# o18_irTransmitter-v03_3_3.net
KiCad netlist of a schematic drawn in EAGLE
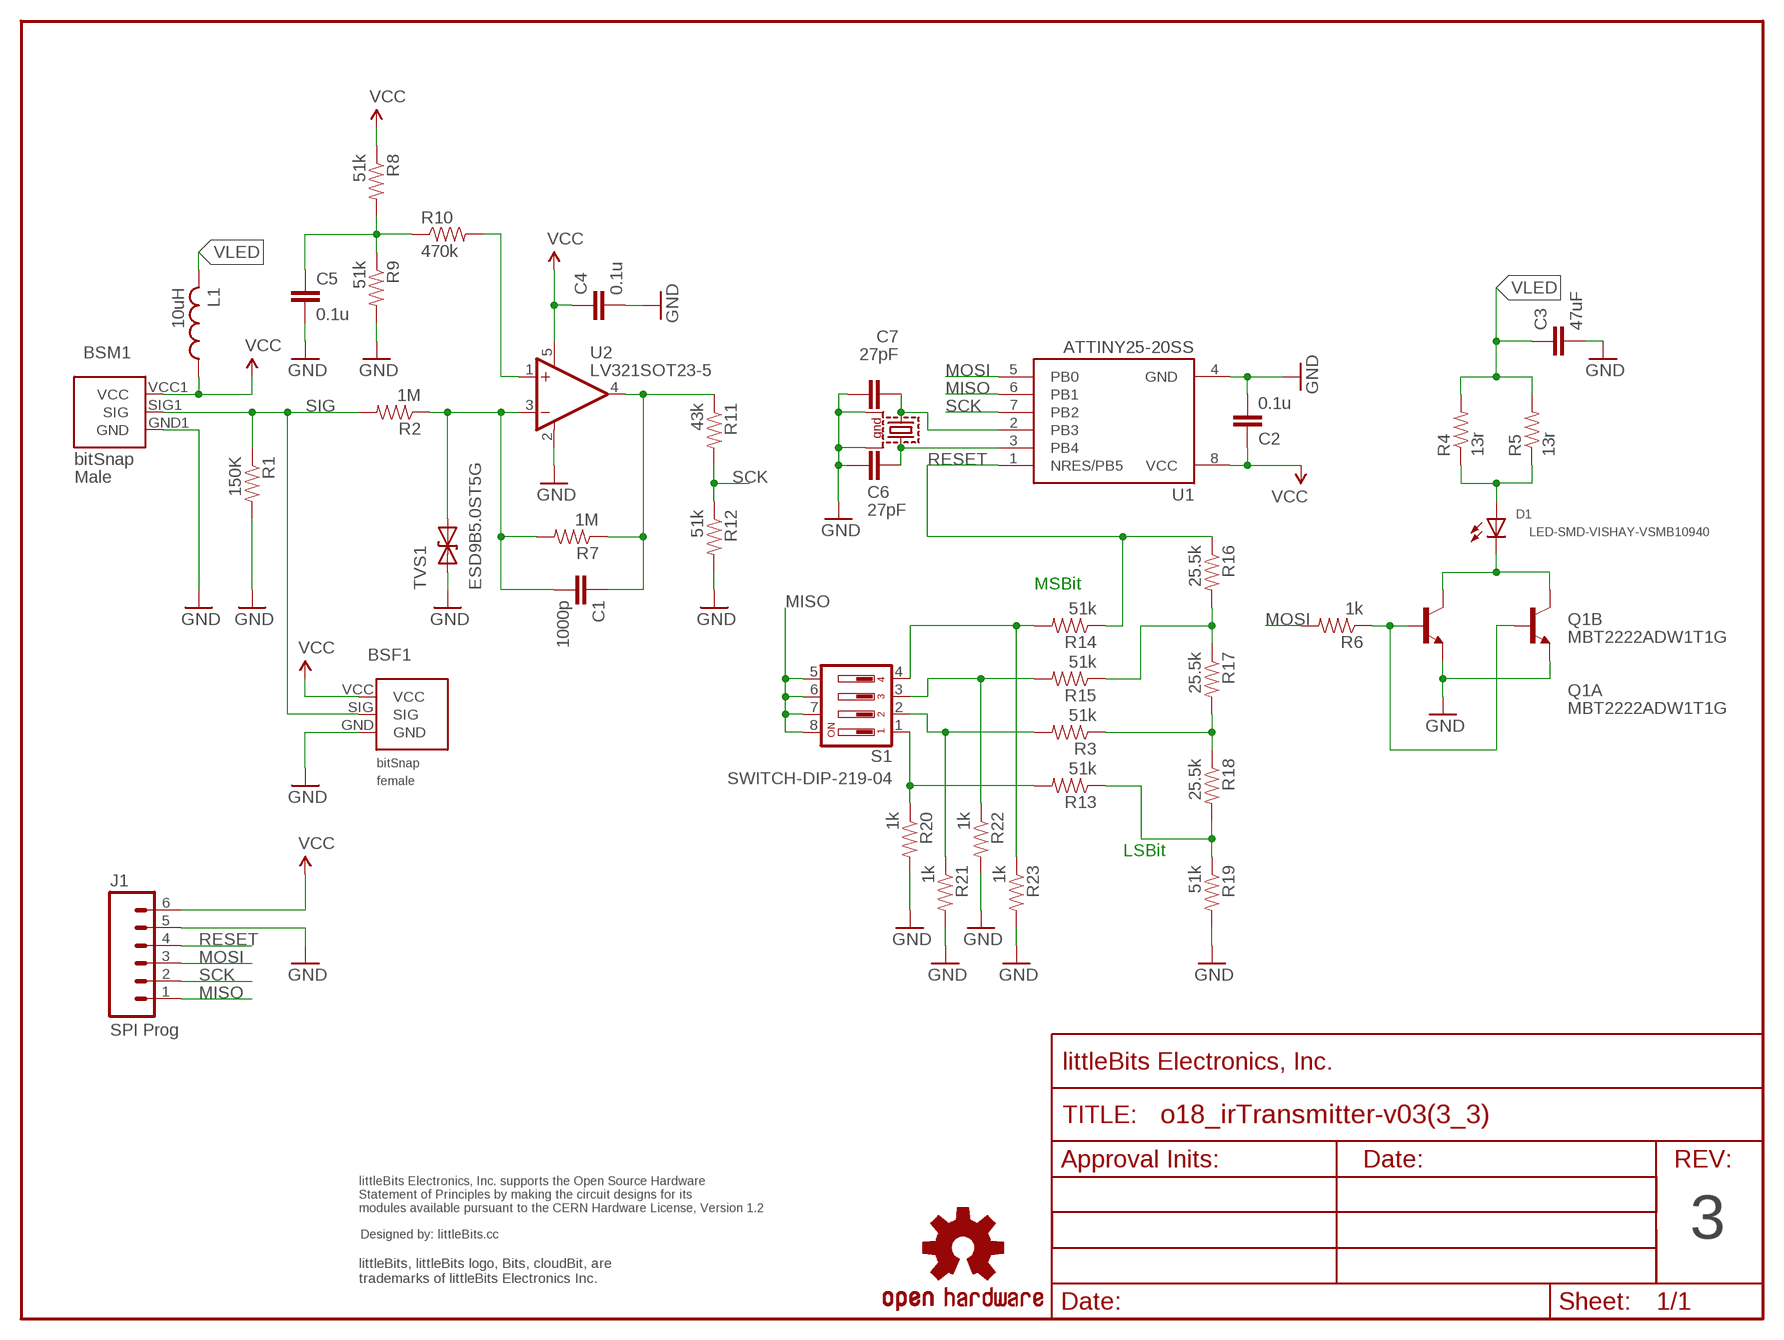
[diagram p0: schematic, sheet 1]

(export (version "E")
  (design (tool "Eeschema 10.0.6"))
  (components
    (comp (ref "BSF1")
      (value "BITSNAP_V03_FEMALE")
      (footprint "eagle-import:BITSNAP_V03_FEMALE")
      (libsource (lib "eagle-import") (part "BITSNAP_V03_FEMALE"))
    )
    (comp (ref "BSM1")
      (value "BITSNAP_V03_MALE")
      (footprint "eagle-import:BITSNAP_V03_MALE")
      (libsource (lib "eagle-import") (part "BITSNAP_V03_MALE"))
    )
    (comp (ref "C1")
      (value "1000p")
      (footprint "eagle-import:CAP-0402")
      (libsource (lib "eagle-import") (part "CAPCAP-0402"))
    )
    (comp (ref "C2")
      (value "0.1u")
      (footprint "eagle-import:CAP-0402")
      (libsource (lib "eagle-import") (part "CAPCAP-0402"))
    )
    (comp (ref "C3")
      (value "47uF")
      (footprint "eagle-import:CAP-1206")
      (libsource (lib "eagle-import") (part "CAPCAP-1206"))
    )
    (comp (ref "C4")
      (value "0.1u")
      (footprint "eagle-import:CAP-0402")
      (libsource (lib "eagle-import") (part "CAPCAP-0402"))
    )
    (comp (ref "C5")
      (value "0.1u")
      (footprint "eagle-import:CAP-0402")
      (libsource (lib "eagle-import") (part "CAPCAP-0402"))
    )
    (comp (ref "C6")
      (value "27pF")
      (footprint "eagle-import:CAP-0402")
      (libsource (lib "eagle-import") (part "CAPCAP-0402"))
    )
    (comp (ref "C7")
      (value "27pF")
      (footprint "eagle-import:CAP-0402")
      (libsource (lib "eagle-import") (part "CAPCAP-0402"))
    )
    (comp (ref "D1")
      (value "LED-SMD-VISHAY-VSMB10940")
      (footprint "eagle-import:LED-SMD-VISHAY-VSMB10940")
      (libsource (lib "eagle-import") (part "LED-SMD-VISHAY-VSMB10940"))
    )
    (comp (ref "J1")
      (value "SPI Prog")
      (footprint "eagle-import:SIP6-SM-0.1IN-NOS.S-MIN")
      (libsource (lib "eagle-import") (part "HRD-60.1INCH_NO_SILKSCREEN_SMALL"))
    )
    (comp (ref "L1")
      (value "10uH")
      (footprint "eagle-import:IND-0805")
      (libsource (lib "eagle-import") (part "INDUCTOR-SMT0805"))
    )
    (comp (ref "Q1")
      (value "MBT2222ADW1T1G")
      (footprint "eagle-import:SOT-363_ONSEMI")
      (libsource (lib "eagle-import") (part "TRANS-BJT_NPN-DUAL-MBT2222ADW1T1-D"))
    )
    (comp (ref "R1")
      (value "150K")
      (footprint "eagle-import:RES-0402")
      (libsource (lib "eagle-import") (part "RESISTOR0402"))
    )
    (comp (ref "R2")
      (value "1M")
      (footprint "eagle-import:RES-0402")
      (libsource (lib "eagle-import") (part "RESISTOR0402"))
    )
    (comp (ref "R3")
      (value "51k")
      (footprint "eagle-import:RES-0402")
      (libsource (lib "eagle-import") (part "RESISTOR0402"))
    )
    (comp (ref "R4")
      (value "13r")
      (footprint "eagle-import:RES-0603")
      (libsource (lib "eagle-import") (part "RESISTOR0603"))
    )
    (comp (ref "R5")
      (value "13r")
      (footprint "eagle-import:RES-0603")
      (libsource (lib "eagle-import") (part "RESISTOR0603"))
    )
    (comp (ref "R6")
      (value "1k")
      (footprint "eagle-import:RES-0402")
      (libsource (lib "eagle-import") (part "RESISTOR0402"))
    )
    (comp (ref "R7")
      (value "1M")
      (footprint "eagle-import:RES-0402")
      (libsource (lib "eagle-import") (part "RESISTOR0402"))
    )
    (comp (ref "R8")
      (value "51k")
      (footprint "eagle-import:RES-0402")
      (libsource (lib "eagle-import") (part "RESISTOR0402"))
    )
    (comp (ref "R9")
      (value "51k")
      (footprint "eagle-import:RES-0402")
      (libsource (lib "eagle-import") (part "RESISTOR0402"))
    )
    (comp (ref "R10")
      (value "470k")
      (footprint "eagle-import:RES-0402")
      (libsource (lib "eagle-import") (part "RESISTOR0402"))
    )
    (comp (ref "R11")
      (value "43k")
      (footprint "eagle-import:RES-0402")
      (libsource (lib "eagle-import") (part "RESISTOR0402"))
    )
    (comp (ref "R12")
      (value "51k")
      (footprint "eagle-import:RES-0402")
      (libsource (lib "eagle-import") (part "RESISTOR0402"))
    )
    (comp (ref "R13")
      (value "51k")
      (footprint "eagle-import:RES-0402")
      (libsource (lib "eagle-import") (part "RESISTOR0402"))
    )
    (comp (ref "R14")
      (value "51k")
      (footprint "eagle-import:RES-0402")
      (libsource (lib "eagle-import") (part "RESISTOR0402"))
    )
    (comp (ref "R15")
      (value "51k")
      (footprint "eagle-import:RES-0402")
      (libsource (lib "eagle-import") (part "RESISTOR0402"))
    )
    (comp (ref "R16")
      (value "25.5k")
      (footprint "eagle-import:RES-0402")
      (libsource (lib "eagle-import") (part "RESISTOR0402"))
    )
    (comp (ref "R17")
      (value "25.5k")
      (footprint "eagle-import:RES-0402")
      (libsource (lib "eagle-import") (part "RESISTOR0402"))
    )
    (comp (ref "R18")
      (value "25.5k")
      (footprint "eagle-import:RES-0402")
      (libsource (lib "eagle-import") (part "RESISTOR0402"))
    )
    (comp (ref "R19")
      (value "51k")
      (footprint "eagle-import:RES-0402")
      (libsource (lib "eagle-import") (part "RESISTOR0402"))
    )
    (comp (ref "R20")
      (value "1k")
      (footprint "eagle-import:RES-0402")
      (libsource (lib "eagle-import") (part "RESISTOR0402"))
    )
    (comp (ref "R21")
      (value "1k")
      (footprint "eagle-import:RES-0402")
      (libsource (lib "eagle-import") (part "RESISTOR0402"))
    )
    (comp (ref "R22")
      (value "1k")
      (footprint "eagle-import:RES-0402")
      (libsource (lib "eagle-import") (part "RESISTOR0402"))
    )
    (comp (ref "R23")
      (value "1k")
      (footprint "eagle-import:RES-0402")
      (libsource (lib "eagle-import") (part "RESISTOR0402"))
    )
    (comp (ref "S1")
      (value "SWITCH-DIP-219-04")
      (footprint "eagle-import:CTS-219-04")
      (libsource (lib "eagle-import") (part "SWITCH-DIP-219-04"))
    )
    (comp (ref "TVS1")
      (value "ESD9B5.0ST5G")
      (footprint "eagle-import:SOD-923")
      (libsource (lib "eagle-import") (part "DIODE-TVSSOD-923"))
    )
    (comp (ref "U$16")
      (value "OSHWCREDIT")
      (footprint "eagle-import:OSHWCREDIT")
      (libsource (lib "eagle-import") (part "OSHWCREDIT"))
    )
    (comp (ref "U$26")
      (value "FRAME-LETTER-OHWOHW")
      (footprint "eagle-import:FABDWG01-OHW")
      (libsource (lib "eagle-import") (part "FRAME-LETTER-OHWOHW"))
    )
    (comp (ref "U$27")
      (value "OSHW-LOGOL")
      (footprint "eagle-import:OSHW-LOGO-L")
      (libsource (lib "eagle-import") (part "OSHW-LOGOL"))
    )
    (comp (ref "U1")
      (value "ATTINY25-20SS")
      (footprint "eagle-import:SOIC08_JEDEC_150MIL")
      (libsource (lib "eagle-import") (part "ATTINY25SS-20"))
    )
    (comp (ref "U2")
      (value "LV321SOT23-5")
      (footprint "eagle-import:SOT23-5")
      (libsource (lib "eagle-import") (part "LV321SOT23-5"))
    )
    (comp (ref "X1")
      (value "7B-8.000MAAJ-T")
      (footprint "eagle-import:CRYSTAL-SMD-7B-SERIES-5X3.2MM")
      (fields (field (name "MFG") "TXC") (field (name "MPN") "7B SERIES"))
      (libsource (lib "eagle-import") (part "CRYSTAL-SMD-7B-SERIES-TXC"))
    )
  )
  (nets
    (net (code "1") (name "/MISO") (class "Default")
      (node (ref "J1") (pin "1") (pinfunction "1_1") (pintype "passive"))
      (node (ref "S1") (pin "5") (pinfunction "5_5") (pintype "passive"))
      (node (ref "S1") (pin "6") (pinfunction "6_6") (pintype "passive"))
      (node (ref "S1") (pin "7") (pinfunction "7_7") (pintype "passive"))
      (node (ref "S1") (pin "8") (pinfunction "8_8") (pintype "passive"))
      (node (ref "U1") (pin "6") (pinfunction "PB1_6") (pintype "bidirectional"))
    )
    (net (code "2") (name "/MOSI") (class "Default")
      (node (ref "J1") (pin "3") (pinfunction "3_3") (pintype "passive"))
      (node (ref "R6") (pin "2") (pinfunction "2_2") (pintype "passive"))
      (node (ref "U1") (pin "5") (pinfunction "PB0_5") (pintype "bidirectional"))
    )
    (net (code "3") (name "/RESET") (class "Default")
      (node (ref "J1") (pin "4") (pinfunction "4_4") (pintype "passive"))
      (node (ref "R14") (pin "1") (pinfunction "1_1") (pintype "passive"))
      (node (ref "R16") (pin "1") (pinfunction "1_1") (pintype "passive"))
      (node (ref "U1") (pin "1") (pinfunction "NRES/PB5_1") (pintype "bidirectional"))
    )
    (net (code "4") (name "/SCK") (class "Default")
      (node (ref "J1") (pin "2") (pinfunction "2_2") (pintype "passive"))
      (node (ref "R11") (pin "2") (pinfunction "2_2") (pintype "passive"))
      (node (ref "R12") (pin "1") (pinfunction "1_1") (pintype "passive"))
      (node (ref "U1") (pin "7") (pinfunction "PB2_7") (pintype "bidirectional"))
    )
    (net (code "5") (name "/SIG") (class "Default")
      (node (ref "BSF1") (pin "SIG") (pinfunction "SIG_SIG") (pintype "bidirectional"))
      (node (ref "BSM1") (pin "SIG1") (pinfunction "SIG_SIG1") (pintype "bidirectional"))
      (node (ref "R1") (pin "1") (pinfunction "1_1") (pintype "passive"))
      (node (ref "R2") (pin "2") (pinfunction "2_2") (pintype "passive"))
    )
    (net (code "6") (name "GND") (class "Default")
      (node (ref "BSF1") (pin "GND") (pinfunction "GND_GND") (pintype "bidirectional"))
      (node (ref "BSM1") (pin "GND1") (pinfunction "GND_GND1") (pintype "bidirectional"))
      (node (ref "C2") (pin "2") (pinfunction "2_2") (pintype "passive"))
      (node (ref "C3") (pin "2") (pinfunction "2_2") (pintype "passive"))
      (node (ref "C4") (pin "2") (pinfunction "2_2") (pintype "passive"))
      (node (ref "C5") (pin "2") (pinfunction "2_2") (pintype "passive"))
      (node (ref "C6") (pin "2") (pinfunction "2_2") (pintype "passive"))
      (node (ref "C7") (pin "1") (pinfunction "1_1") (pintype "passive"))
      (node (ref "J1") (pin "5") (pinfunction "5_5") (pintype "passive"))
      (node (ref "Q1") (pin "1") (pinfunction "E_1") (pintype "passive"))
      (node (ref "Q1") (pin "4") (pinfunction "E_4") (pintype "passive"))
      (node (ref "R1") (pin "2") (pinfunction "2_2") (pintype "passive"))
      (node (ref "R12") (pin "2") (pinfunction "2_2") (pintype "passive"))
      (node (ref "R19") (pin "2") (pinfunction "2_2") (pintype "passive"))
      (node (ref "R20") (pin "2") (pinfunction "2_2") (pintype "passive"))
      (node (ref "R21") (pin "2") (pinfunction "2_2") (pintype "passive"))
      (node (ref "R22") (pin "2") (pinfunction "2_2") (pintype "passive"))
      (node (ref "R23") (pin "2") (pinfunction "2_2") (pintype "passive"))
      (node (ref "R9") (pin "2") (pinfunction "2_2") (pintype "passive"))
      (node (ref "TVS1") (pin "1") (pinfunction "A_1") (pintype "passive"))
      (node (ref "U1") (pin "4") (pinfunction "GND_4") (pintype "power_in"))
      (node (ref "U2") (pin "2") (pinfunction "V-_2") (pintype "power_in"))
      (node (ref "X1") (pin "P$2") (pinfunction "2_P$2") (pintype "passive"))
      (node (ref "X1") (pin "P$4") (pinfunction "4_P$4") (pintype "passive"))
    )
    (net (code "7") (name "Net-(C5-Pad1)") (class "Default")
      (node (ref "C5") (pin "1") (pinfunction "1_1") (pintype "passive"))
      (node (ref "R10") (pin "1") (pinfunction "1_1") (pintype "passive"))
      (node (ref "R8") (pin "2") (pinfunction "2_2") (pintype "passive"))
      (node (ref "R9") (pin "1") (pinfunction "1_1") (pintype "passive"))
    )
    (net (code "8") (name "Net-(D1-PadA)") (class "Default")
      (node (ref "D1") (pin "A") (pinfunction "A_A") (pintype "passive"))
      (node (ref "R4") (pin "1") (pinfunction "1_1") (pintype "passive"))
      (node (ref "R5") (pin "1") (pinfunction "1_1") (pintype "passive"))
    )
    (net (code "9") (name "Net-(Q1A-B)") (class "Default")
      (node (ref "Q1") (pin "2") (pinfunction "B_2") (pintype "passive"))
      (node (ref "Q1") (pin "5") (pinfunction "B_5") (pintype "passive"))
      (node (ref "R6") (pin "1") (pinfunction "1_1") (pintype "passive"))
    )
    (net (code "10") (name "Net-(Q1A-C)") (class "Default")
      (node (ref "D1") (pin "C") (pinfunction "C_C") (pintype "passive"))
      (node (ref "Q1") (pin "3") (pinfunction "C_3") (pintype "passive"))
      (node (ref "Q1") (pin "6") (pinfunction "C_6") (pintype "passive"))
    )
    (net (code "11") (name "Net-(R13-Pad1)") (class "Default")
      (node (ref "R13") (pin "1") (pinfunction "1_1") (pintype "passive"))
      (node (ref "R18") (pin "2") (pinfunction "2_2") (pintype "passive"))
      (node (ref "R19") (pin "1") (pinfunction "1_1") (pintype "passive"))
    )
    (net (code "12") (name "Net-(R13-Pad2)") (class "Default")
      (node (ref "R13") (pin "2") (pinfunction "2_2") (pintype "passive"))
      (node (ref "R20") (pin "1") (pinfunction "1_1") (pintype "passive"))
      (node (ref "S1") (pin "1") (pinfunction "1_1") (pintype "passive"))
    )
    (net (code "13") (name "Net-(R14-Pad2)") (class "Default")
      (node (ref "R14") (pin "2") (pinfunction "2_2") (pintype "passive"))
      (node (ref "R23") (pin "1") (pinfunction "1_1") (pintype "passive"))
      (node (ref "S1") (pin "4") (pinfunction "4_4") (pintype "passive"))
    )
    (net (code "14") (name "Net-(R15-Pad1)") (class "Default")
      (node (ref "R15") (pin "1") (pinfunction "1_1") (pintype "passive"))
      (node (ref "R16") (pin "2") (pinfunction "2_2") (pintype "passive"))
      (node (ref "R17") (pin "1") (pinfunction "1_1") (pintype "passive"))
    )
    (net (code "15") (name "Net-(R15-Pad2)") (class "Default")
      (node (ref "R15") (pin "2") (pinfunction "2_2") (pintype "passive"))
      (node (ref "R22") (pin "1") (pinfunction "1_1") (pintype "passive"))
      (node (ref "S1") (pin "3") (pinfunction "3_3") (pintype "passive"))
    )
    (net (code "16") (name "Net-(R17-Pad2)") (class "Default")
      (node (ref "R17") (pin "2") (pinfunction "2_2") (pintype "passive"))
      (node (ref "R18") (pin "1") (pinfunction "1_1") (pintype "passive"))
      (node (ref "R3") (pin "1") (pinfunction "1_1") (pintype "passive"))
    )
    (net (code "17") (name "Net-(R21-Pad1)") (class "Default")
      (node (ref "R21") (pin "1") (pinfunction "1_1") (pintype "passive"))
      (node (ref "R3") (pin "2") (pinfunction "2_2") (pintype "passive"))
      (node (ref "S1") (pin "2") (pinfunction "2_2") (pintype "passive"))
    )
    (net (code "18") (name "Net-(TVS1-C)") (class "Default")
      (node (ref "C1") (pin "2") (pinfunction "2_2") (pintype "passive"))
      (node (ref "R2") (pin "1") (pinfunction "1_1") (pintype "passive"))
      (node (ref "R7") (pin "2") (pinfunction "2_2") (pintype "passive"))
      (node (ref "TVS1") (pin "2") (pinfunction "C_2") (pintype "passive"))
      (node (ref "U2") (pin "3") (pinfunction "-IN_3") (pintype "input"))
    )
    (net (code "19") (name "Net-(U1-PB3)") (class "Default")
      (node (ref "C7") (pin "2") (pinfunction "2_2") (pintype "passive"))
      (node (ref "U1") (pin "2") (pinfunction "PB3_2") (pintype "bidirectional"))
      (node (ref "X1") (pin "P$1") (pinfunction "1_P$1") (pintype "passive"))
    )
    (net (code "20") (name "Net-(U1-PB4)") (class "Default")
      (node (ref "C6") (pin "1") (pinfunction "1_1") (pintype "passive"))
      (node (ref "U1") (pin "3") (pinfunction "PB4_3") (pintype "bidirectional"))
      (node (ref "X1") (pin "P$3") (pinfunction "3_P$3") (pintype "passive"))
    )
    (net (code "21") (name "Net-(U2-+IN)") (class "Default")
      (node (ref "R10") (pin "2") (pinfunction "2_2") (pintype "passive"))
      (node (ref "U2") (pin "1") (pinfunction "+IN_1") (pintype "input"))
    )
    (net (code "22") (name "Net-(U2-OUT)") (class "Default")
      (node (ref "C1") (pin "1") (pinfunction "1_1") (pintype "passive"))
      (node (ref "R11") (pin "1") (pinfunction "1_1") (pintype "passive"))
      (node (ref "R7") (pin "1") (pinfunction "1_1") (pintype "passive"))
      (node (ref "U2") (pin "4") (pinfunction "OUT_4") (pintype "output"))
    )
    (net (code "23") (name "VCC") (class "Default")
      (node (ref "BSF1") (pin "VCC") (pinfunction "VCC_VCC") (pintype "bidirectional"))
      (node (ref "BSM1") (pin "VCC1") (pinfunction "VCC_VCC1") (pintype "bidirectional"))
      (node (ref "C2") (pin "1") (pinfunction "1_1") (pintype "passive"))
      (node (ref "C4") (pin "1") (pinfunction "1_1") (pintype "passive"))
      (node (ref "J1") (pin "6") (pinfunction "6_6") (pintype "passive"))
      (node (ref "L1") (pin "1") (pinfunction "1_1") (pintype "passive"))
      (node (ref "R8") (pin "1") (pinfunction "1_1") (pintype "passive"))
      (node (ref "U1") (pin "8") (pinfunction "VCC_8") (pintype "power_in"))
      (node (ref "U2") (pin "5") (pinfunction "V+_5") (pintype "power_in"))
    )
    (net (code "24") (name "VLED") (class "Default")
      (node (ref "C3") (pin "1") (pinfunction "1_1") (pintype "passive"))
      (node (ref "L1") (pin "2") (pinfunction "2_2") (pintype "passive"))
      (node (ref "R4") (pin "2") (pinfunction "2_2") (pintype "passive"))
      (node (ref "R5") (pin "2") (pinfunction "2_2") (pintype "passive"))
    )
  )
)
